# Flexi_encoder_BOB.net
KiCad netlist of a schematic drawn in Altium Designer
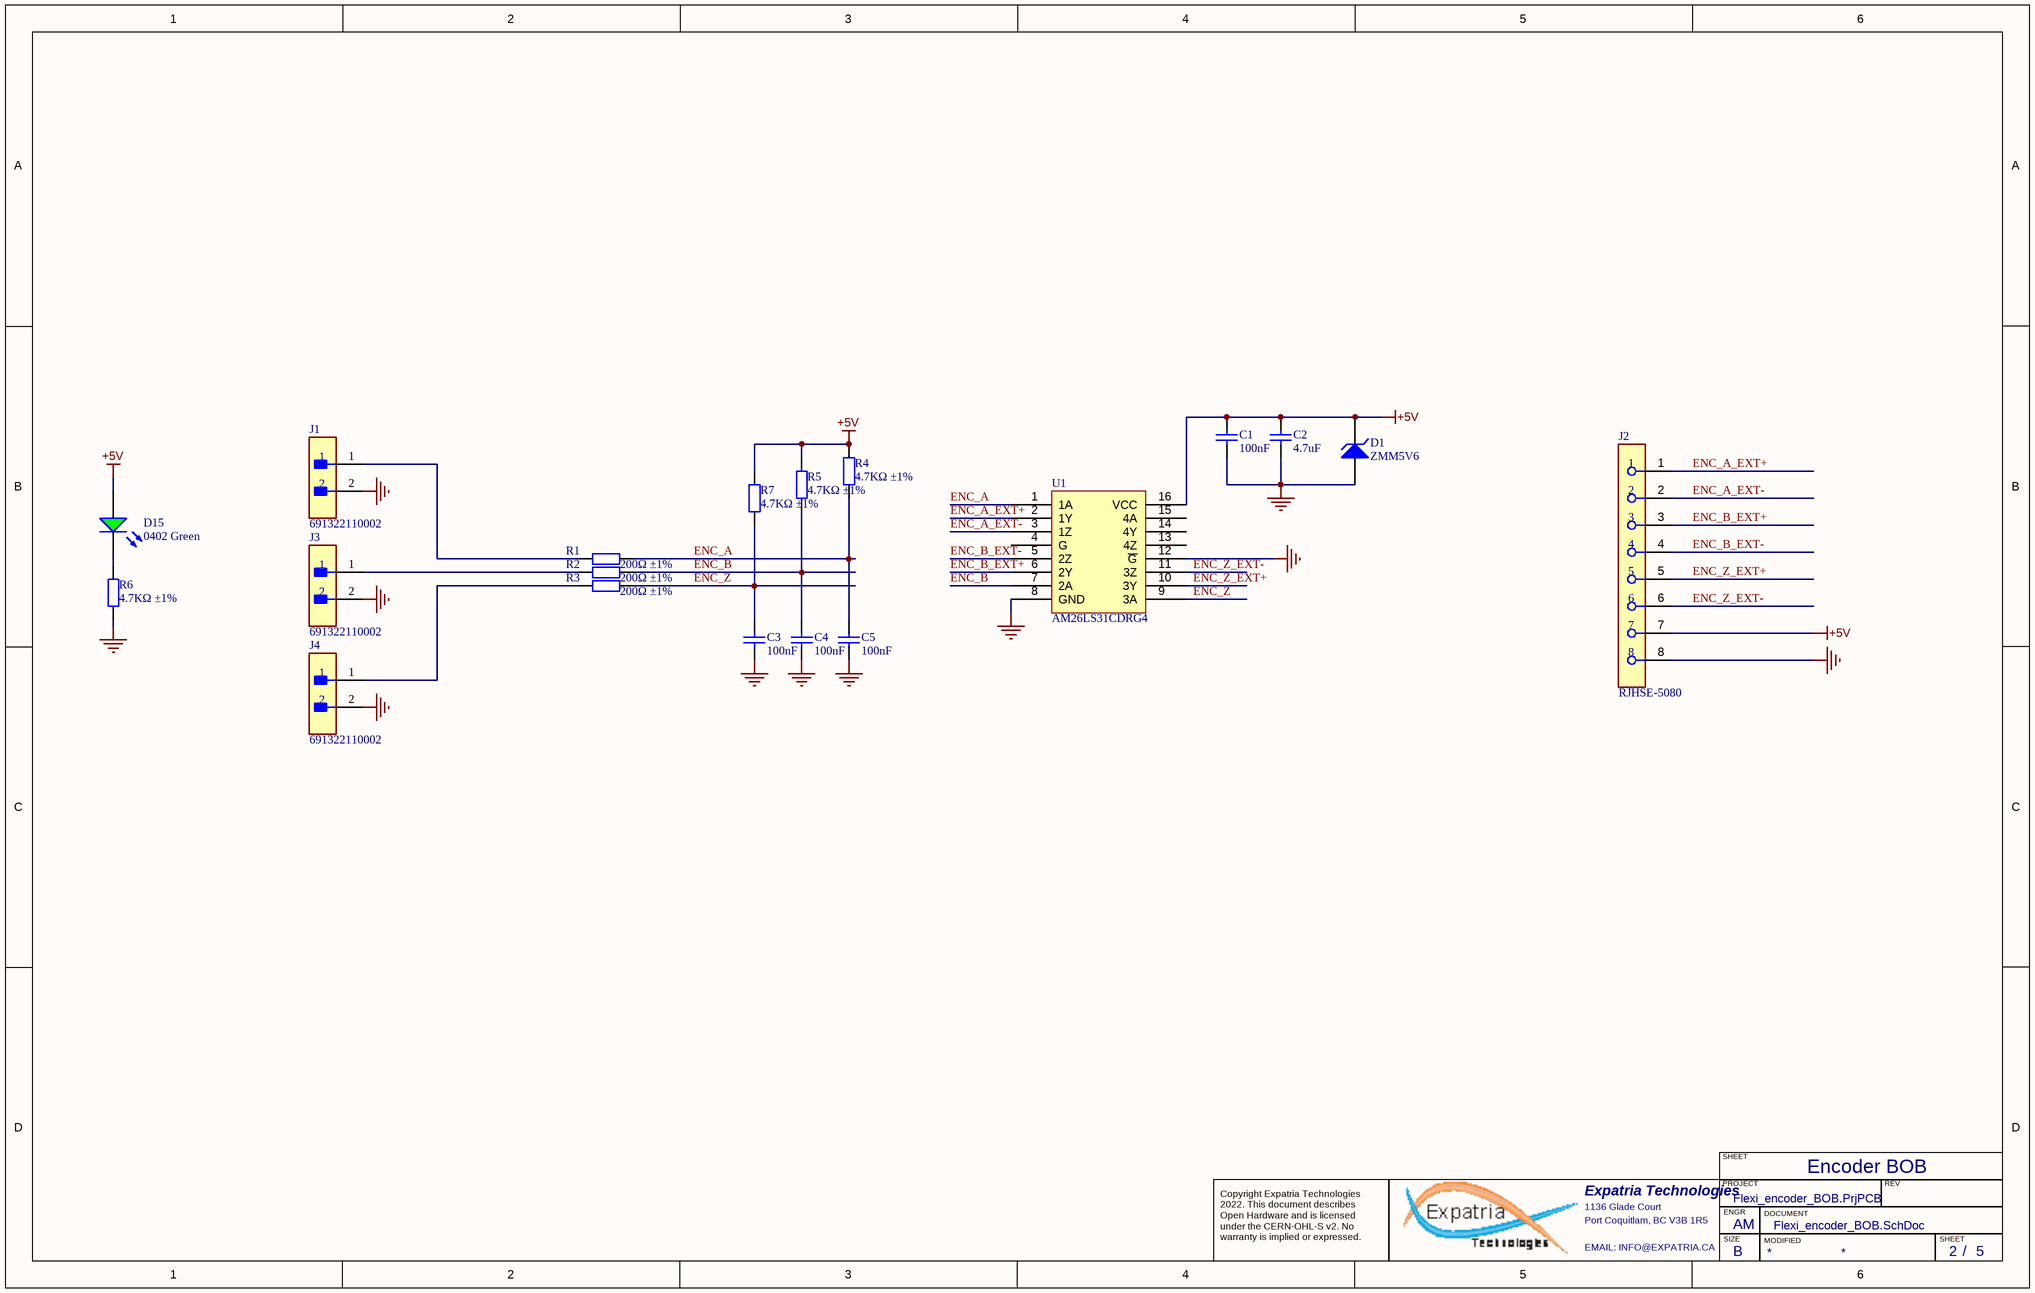
[diagram p0: Flexi_encoder_BOB.SchDoc]

(export (version "E")
  (design (tool "Eeschema 10.0.6"))
  (components
    (comp (ref "C1")
      (value "100nF")
      (footprint "0402_C")
      (description "Chip capacitors")
      (fields
        (field (name "MANUFACTURER") "Samsung Electro-Mechanics")
        (field (name "PARTNUMBER") "CL05B104KO5NNNC")
      )
      (libsource (lib "Cap") (part "0402 100nF (104) 10% 16V"))
    )
    (comp (ref "C2")
      (value "4.7uF")
      (footprint "0402_C")
      (description "Chip capacitor")
      (fields
        (field (name "MANUFACTURER") "Samsung Electro-Mechanics")
        (field (name "PARTNUMBER") "CL05A475MP5NRNC")
      )
      (libsource (lib "Cap") (part "0402 4.7uF (475) 20% 10V"))
    )
    (comp (ref "C3")
      (value "100nF")
      (footprint "0402_C")
      (description "Chip capacitors")
      (fields
        (field (name "MANUFACTURER") "Samsung Electro-Mechanics")
        (field (name "PARTNUMBER") "CL05B104KO5NNNC")
      )
      (libsource (lib "Cap") (part "0402 100nF (104) 10% 16V"))
    )
    (comp (ref "C4")
      (value "100nF")
      (footprint "0402_C")
      (description "Chip capacitors")
      (fields
        (field (name "MANUFACTURER") "Samsung Electro-Mechanics")
        (field (name "PARTNUMBER") "CL05B104KO5NNNC")
      )
      (libsource (lib "Cap") (part "0402 100nF (104) 10% 16V"))
    )
    (comp (ref "C5")
      (value "100nF")
      (footprint "0402_C")
      (description "Chip capacitors")
      (fields
        (field (name "MANUFACTURER") "Samsung Electro-Mechanics")
        (field (name "PARTNUMBER") "CL05B104KO5NNNC")
      )
      (libsource (lib "Cap") (part "0402 100nF (104) 10% 16V"))
    )
    (comp (ref "D1")
      (value "ZMM5V6")
      (footprint "LL-34")
      (description "500mW - 0.1uA @ 1V 5.6V LL-34 Zener Diodes ROHS")
      (libsource (lib "Zener") (part "LL-34 ZMM5V6"))
    )
    (comp (ref "D15")
      (value "0402 Green")
      (footprint "LED 0402_1005 RED")
      (description "LED")
      (libsource (lib "LED") (part "0402 LED Green"))
    )
    (comp (ref "J1")
      (value "691322110002")
      (footprint "FP-691322110002-MFG")
      (description "TERM BLOCK HDR 2POS 90DEG 3.5MM")
      (fields (field (name "VOLTAGE") "300V"))
      (libsource (lib "Altium Content Vault") (part "3bc925449376181038e59eaffc5286c"))
    )
    (comp (ref "J2")
      (value "RJHSE-5080")
      (footprint "FP-RJHSE-5080-MFG")
      (description "CONN MOD JACK 8P8C R/A UNSHLD")
      (fields
        (field (name "MANUFACTURER PART NUMBER") "E5J88-00LJG2-L")
        (field (name "MANUFACTURER") "Pulse Electronics Network")
      )
      (libsource (lib "Altium Content Vault") (part "b0a0b555dd3abf3683e7c330df25cc4"))
    )
    (comp (ref "J3")
      (value "691322110002")
      (footprint "FP-691322110002-MFG")
      (description "TERM BLOCK HDR 2POS 90DEG 3.5MM")
      (fields (field (name "VOLTAGE") "300V"))
      (libsource (lib "Altium Content Vault") (part "3bc925449376181038e59eaffc5286c"))
    )
    (comp (ref "J4")
      (value "691322110002")
      (footprint "FP-691322110002-MFG")
      (description "TERM BLOCK HDR 2POS 90DEG 3.5MM")
      (fields (field (name "VOLTAGE") "300V"))
      (libsource (lib "Altium Content Vault") (part "3bc925449376181038e59eaffc5286c"))
    )
    (comp (ref "R1")
      (value "200Ω ±1%")
      (footprint "0402_R")
      (description "Chip resistor")
      (fields (field (name "MANUFACTURER") "Uniroyal Elec") (field (name "PARTNUMBER") "0402WGF2000TCE"))
      (libsource (lib "RES") (part "0402 200R (2000) 1%"))
    )
    (comp (ref "R2")
      (value "200Ω ±1%")
      (footprint "0402_R")
      (description "Chip resistor")
      (fields (field (name "MANUFACTURER") "Uniroyal Elec") (field (name "PARTNUMBER") "0402WGF2000TCE"))
      (libsource (lib "RES") (part "0402 200R (2000) 1%"))
    )
    (comp (ref "R3")
      (value "200Ω ±1%")
      (footprint "0402_R")
      (description "Chip resistor")
      (fields (field (name "MANUFACTURER") "Uniroyal Elec") (field (name "PARTNUMBER") "0402WGF2000TCE"))
      (libsource (lib "RES") (part "0402 200R (2000) 1%"))
    )
    (comp (ref "R4")
      (value "4.7KΩ ±1%")
      (footprint "0402_R")
      (description "Chip resistor")
      (fields (field (name "MANUFACTURER") "Uniroyal Elec") (field (name "PARTNUMBER") "0402WGF4701TCE"))
      (libsource (lib "RES") (part "0402 4.7K (4701) 1%"))
    )
    (comp (ref "R5")
      (value "4.7KΩ ±1%")
      (footprint "0402_R")
      (description "Chip resistor")
      (fields (field (name "MANUFACTURER") "Uniroyal Elec") (field (name "PARTNUMBER") "0402WGF4701TCE"))
      (libsource (lib "RES") (part "0402 4.7K (4701) 1%"))
    )
    (comp (ref "R6")
      (value "4.7KΩ ±1%")
      (footprint "0402_R")
      (description "Chip resistor")
      (fields (field (name "MANUFACTURER") "Uniroyal Elec") (field (name "PARTNUMBER") "0402WGF4701TCE"))
      (libsource (lib "RES") (part "0402 4.7K (4701) 1%"))
    )
    (comp (ref "R7")
      (value "4.7KΩ ±1%")
      (footprint "0402_R")
      (description "Chip resistor")
      (fields (field (name "MANUFACTURER") "Uniroyal Elec") (field (name "PARTNUMBER") "0402WGF4701TCE"))
      (libsource (lib "RES") (part "0402 4.7K (4701) 1%"))
    )
    (comp (ref "U1")
      (value "AM26LS31CDRG4")
      (footprint "SOIC-16_150mil")
      (description "4/0 Driver - RS422, RS485 16-SOIC")
      (libsource (lib "IC") (part "AM26LS31CDRG4_[C6179]"))
    )
  )
  (nets
    (net (code "1") (name "+5V") (class "Default")
      (node (ref "C1") (pin "1") (pinfunction "1_1") (pintype "passive"))
      (node (ref "C2") (pin "1") (pinfunction "1_1") (pintype "passive"))
      (node (ref "D1") (pin "2") (pinfunction "K_2") (pintype "passive"))
      (node (ref "D15") (pin "A") (pinfunction "A_A") (pintype "passive"))
      (node (ref "J2") (pin "7") (pinfunction "7_7") (pintype "passive"))
      (node (ref "R4") (pin "2") (pinfunction "2_2") (pintype "passive"))
      (node (ref "R5") (pin "2") (pinfunction "2_2") (pintype "passive"))
      (node (ref "R7") (pin "2") (pinfunction "2_2") (pintype "passive"))
      (node (ref "U1") (pin "16") (pinfunction "VCC_16") (pintype "passive"))
    )
    (net (code "2") (name "/ENC_A") (class "Default")
      (node (ref "C5") (pin "1") (pinfunction "1_1") (pintype "passive"))
      (node (ref "R1") (pin "1") (pinfunction "1_1") (pintype "passive"))
      (node (ref "R4") (pin "1") (pinfunction "1_1") (pintype "passive"))
      (node (ref "U1") (pin "1") (pinfunction "1A_1") (pintype "passive"))
    )
    (net (code "3") (name "/ENC_A_EXT+") (class "Default")
      (node (ref "J2") (pin "1") (pinfunction "1_1") (pintype "passive"))
      (node (ref "U1") (pin "2") (pinfunction "1Y_2") (pintype "passive"))
    )
    (net (code "4") (name "/ENC_A_EXT-") (class "Default")
      (node (ref "J2") (pin "2") (pinfunction "2_2") (pintype "passive"))
      (node (ref "U1") (pin "3") (pinfunction "1Z_3") (pintype "passive"))
    )
    (net (code "5") (name "/ENC_B") (class "Default")
      (node (ref "C4") (pin "1") (pinfunction "1_1") (pintype "passive"))
      (node (ref "R2") (pin "1") (pinfunction "1_1") (pintype "passive"))
      (node (ref "R5") (pin "1") (pinfunction "1_1") (pintype "passive"))
      (node (ref "U1") (pin "7") (pinfunction "2A_7") (pintype "passive"))
    )
    (net (code "6") (name "/ENC_B_EXT+") (class "Default")
      (node (ref "J2") (pin "3") (pinfunction "3_3") (pintype "passive"))
      (node (ref "U1") (pin "6") (pinfunction "2Y_6") (pintype "passive"))
    )
    (net (code "7") (name "/ENC_B_EXT-") (class "Default")
      (node (ref "J2") (pin "4") (pinfunction "4_4") (pintype "passive"))
      (node (ref "U1") (pin "5") (pinfunction "2Z_5") (pintype "passive"))
    )
    (net (code "8") (name "/ENC_Z") (class "Default")
      (node (ref "C3") (pin "1") (pinfunction "1_1") (pintype "passive"))
      (node (ref "R3") (pin "1") (pinfunction "1_1") (pintype "passive"))
      (node (ref "R7") (pin "1") (pinfunction "1_1") (pintype "passive"))
      (node (ref "U1") (pin "9") (pinfunction "3A_9") (pintype "passive"))
    )
    (net (code "9") (name "/ENC_Z_EXT+") (class "Default")
      (node (ref "J2") (pin "5") (pinfunction "5_5") (pintype "passive"))
      (node (ref "U1") (pin "10") (pinfunction "3Y_10") (pintype "passive"))
    )
    (net (code "10") (name "/ENC_Z_EXT-") (class "Default")
      (node (ref "J2") (pin "6") (pinfunction "6_6") (pintype "passive"))
      (node (ref "U1") (pin "11") (pinfunction "3Z_11") (pintype "passive"))
    )
    (net (code "11") (name "GND") (class "Default")
      (node (ref "C1") (pin "2") (pinfunction "2_2") (pintype "passive"))
      (node (ref "C2") (pin "2") (pinfunction "2_2") (pintype "passive"))
      (node (ref "C3") (pin "2") (pinfunction "2_2") (pintype "passive"))
      (node (ref "C4") (pin "2") (pinfunction "2_2") (pintype "passive"))
      (node (ref "C5") (pin "2") (pinfunction "2_2") (pintype "passive"))
      (node (ref "D1") (pin "1") (pinfunction "A_1") (pintype "passive"))
      (node (ref "J1") (pin "2") (pinfunction "2_2") (pintype "passive"))
      (node (ref "J2") (pin "8") (pinfunction "8_8") (pintype "passive"))
      (node (ref "J3") (pin "2") (pinfunction "2_2") (pintype "passive"))
      (node (ref "J4") (pin "2") (pinfunction "2_2") (pintype "passive"))
      (node (ref "R6") (pin "1") (pinfunction "1_1") (pintype "passive"))
      (node (ref "U1") (pin "12") (pinfunction "~{G}_12") (pintype "passive"))
      (node (ref "U1") (pin "8") (pinfunction "GND_8") (pintype "passive"))
    )
    (net (code "12") (name "Net-(D15-PadK)") (class "Default")
      (node (ref "D15") (pin "K") (pinfunction "K_K") (pintype "passive"))
      (node (ref "R6") (pin "2") (pinfunction "2_2") (pintype "passive"))
    )
    (net (code "13") (name "Net-(J1-Pad1)") (class "Default")
      (node (ref "J1") (pin "1") (pinfunction "1_1") (pintype "passive"))
      (node (ref "R1") (pin "2") (pinfunction "2_2") (pintype "passive"))
    )
    (net (code "14") (name "Net-(J3-Pad1)") (class "Default")
      (node (ref "J3") (pin "1") (pinfunction "1_1") (pintype "passive"))
      (node (ref "R2") (pin "2") (pinfunction "2_2") (pintype "passive"))
    )
    (net (code "15") (name "Net-(J4-Pad1)") (class "Default")
      (node (ref "J4") (pin "1") (pinfunction "1_1") (pintype "passive"))
      (node (ref "R3") (pin "2") (pinfunction "2_2") (pintype "passive"))
    )
    (net (code "16") (name "unconnected-(U1-4A-Pad15)") (class "Default")
      (node (ref "U1") (pin "15") (pinfunction "4A_15") (pintype "passive"))
    )
    (net (code "17") (name "unconnected-(U1-4Y-Pad14)") (class "Default")
      (node (ref "U1") (pin "14") (pinfunction "4Y_14") (pintype "passive"))
    )
    (net (code "18") (name "unconnected-(U1-4Z-Pad13)") (class "Default")
      (node (ref "U1") (pin "13") (pinfunction "4Z_13") (pintype "passive"))
    )
    (net (code "19") (name "unconnected-(U1-G-Pad4)") (class "Default")
      (node (ref "U1") (pin "4") (pinfunction "G_4") (pintype "passive"))
    )
  )
)
